# PAM8320_Amplifier_Board_R1.net
KiCad netlist of a schematic drawn in EAGLE
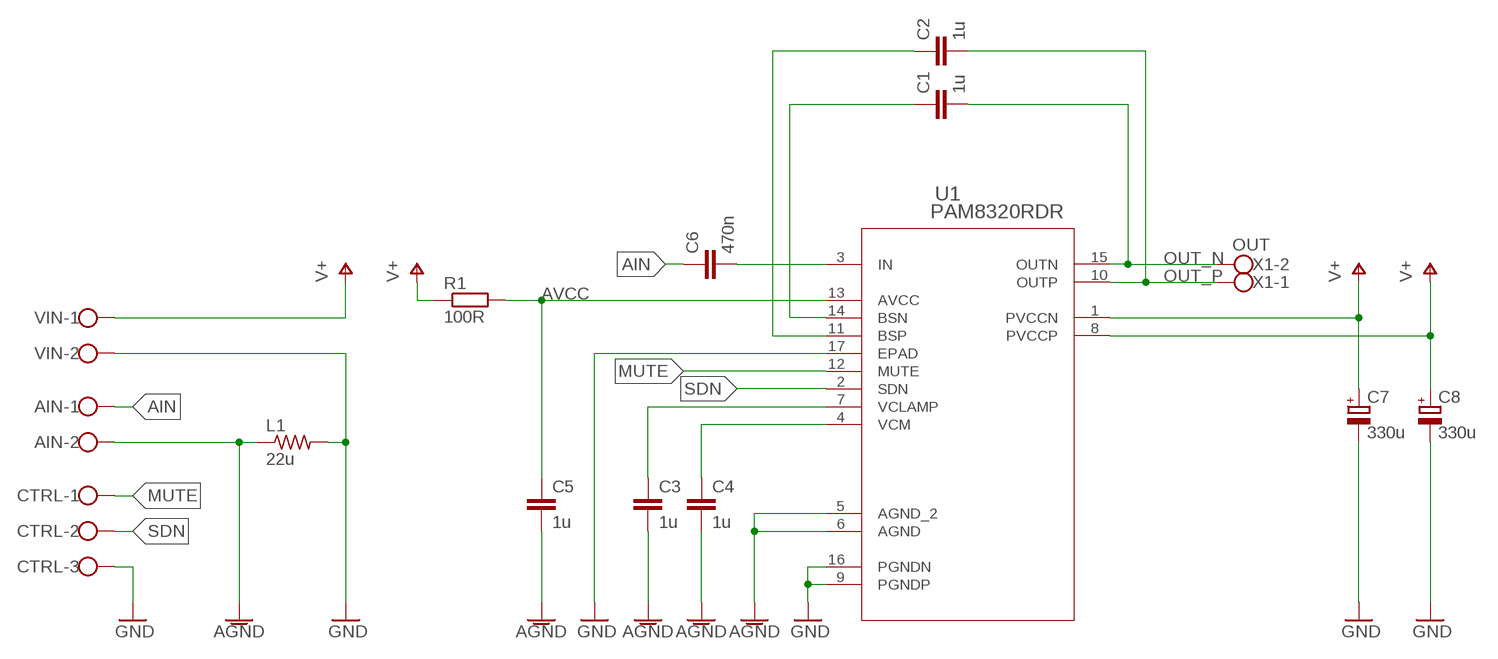
[diagram p0: schematic, sheet 1]

(export (version "E")
  (design (tool "Eeschema 10.0.6"))
  (components
    (comp (ref "AIN")
      (value "W237-102")
      (footprint "eagle-import:W237-102")
      (fields (field (name "MPN") "237-102"))
      (libsource (lib "eagle-import") (part "W237-102"))
    )
    (comp (ref "C1")
      (value "1u")
      (footprint "eagle-import:C1206")
      (libsource (lib "eagle-import") (part "C-EUC1206"))
    )
    (comp (ref "C2")
      (value "1u")
      (footprint "eagle-import:C1206")
      (libsource (lib "eagle-import") (part "C-EUC1206"))
    )
    (comp (ref "C3")
      (value "1u")
      (footprint "eagle-import:C1206")
      (libsource (lib "eagle-import") (part "C-EUC1206"))
    )
    (comp (ref "C4")
      (value "1u")
      (footprint "eagle-import:C1206")
      (libsource (lib "eagle-import") (part "C-EUC1206"))
    )
    (comp (ref "C5")
      (value "1u")
      (footprint "eagle-import:C1206")
      (libsource (lib "eagle-import") (part "C-EUC1206"))
    )
    (comp (ref "C6")
      (value "470n")
      (footprint "eagle-import:C1206")
      (libsource (lib "eagle-import") (part "C-EUC1206"))
    )
    (comp (ref "C7")
      (value "330u")
      (footprint "eagle-import:E3,5-8")
      (libsource (lib "eagle-import") (part "CPOL-EUE3.5-8"))
    )
    (comp (ref "C8")
      (value "330u")
      (footprint "eagle-import:E3,5-8")
      (libsource (lib "eagle-import") (part "CPOL-EUE3.5-8"))
    )
    (comp (ref "CTRL")
      (value "W237-103")
      (footprint "eagle-import:W237-103")
      (fields (field (name "MPN") "237-103"))
      (libsource (lib "eagle-import") (part "W237-103"))
    )
    (comp (ref "L1")
      (value "22u")
      (footprint "eagle-import:R0805")
      (libsource (lib "eagle-import") (part "R-US_R0805"))
    )
    (comp (ref "R1")
      (value "100R")
      (footprint "eagle-import:R0603")
      (libsource (lib "eagle-import") (part "R-EU_R0603"))
    )
    (comp (ref "U1")
      (value "PAM8320RDR")
      (footprint "eagle-import:SO-16EP_3P9X9P9_DIO")
      (fields (field (name "COPYRIGHT") "Copyright (C) 2023 Ultra Librarian. All rights reserved."))
      (libsource (lib "eagle-import") (part "PAM8320RDR"))
    )
    (comp (ref "VIN")
      (value "W237-102")
      (footprint "eagle-import:W237-102")
      (fields (field (name "MPN") "237-102"))
      (libsource (lib "eagle-import") (part "W237-102"))
    )
    (comp (ref "X1")
      (value "OUT")
      (footprint "eagle-import:W237-102")
      (fields (field (name "MPN") "237-102"))
      (libsource (lib "eagle-import") (part "W237-102"))
    )
  )
  (nets
    (net (code "1") (name "/AVCC") (class "Default")
      (node (ref "C5") (pin "1") (pinfunction "1_1") (pintype "passive"))
      (node (ref "R1") (pin "2") (pinfunction "2_2") (pintype "passive"))
      (node (ref "U1") (pin "13") (pinfunction "AVCC_13") (pintype "passive"))
    )
    (net (code "2") (name "/OUT_N") (class "Default")
      (node (ref "C1") (pin "2") (pinfunction "2_2") (pintype "passive"))
      (node (ref "U1") (pin "15") (pinfunction "OUTN_15") (pintype "output"))
      (node (ref "X1") (pin "2") (pinfunction "KL_2") (pintype "passive"))
    )
    (net (code "3") (name "/OUT_P") (class "Default")
      (node (ref "C2") (pin "2") (pinfunction "2_2") (pintype "passive"))
      (node (ref "U1") (pin "10") (pinfunction "OUTP_10") (pintype "output"))
      (node (ref "X1") (pin "1") (pinfunction "KL_1") (pintype "passive"))
    )
    (net (code "4") (name "AGND") (class "Default")
      (node (ref "AIN") (pin "2") (pinfunction "KL_2") (pintype "passive"))
      (node (ref "C3") (pin "2") (pinfunction "2_2") (pintype "passive"))
      (node (ref "C4") (pin "2") (pinfunction "2_2") (pintype "passive"))
      (node (ref "C5") (pin "2") (pinfunction "2_2") (pintype "passive"))
      (node (ref "L1") (pin "1") (pinfunction "1_1") (pintype "passive"))
      (node (ref "U1") (pin "5") (pinfunction "AGND_2_5") (pintype "passive"))
      (node (ref "U1") (pin "6") (pinfunction "AGND_6") (pintype "passive"))
    )
    (net (code "5") (name "AIN") (class "Default")
      (node (ref "AIN") (pin "1") (pinfunction "KL_1") (pintype "passive"))
      (node (ref "C6") (pin "1") (pinfunction "1_1") (pintype "passive"))
    )
    (net (code "6") (name "GND") (class "Default")
      (node (ref "C7") (pin "-") (pinfunction "-_-") (pintype "passive"))
      (node (ref "C8") (pin "-") (pinfunction "-_-") (pintype "passive"))
      (node (ref "CTRL") (pin "3") (pinfunction "KL_3") (pintype "passive"))
      (node (ref "L1") (pin "2") (pinfunction "2_2") (pintype "passive"))
      (node (ref "U1") (pin "16") (pinfunction "PGNDN_16") (pintype "passive"))
      (node (ref "U1") (pin "17") (pinfunction "EPAD_17") (pintype "passive"))
      (node (ref "U1") (pin "9") (pinfunction "PGNDP_9") (pintype "passive"))
      (node (ref "VIN") (pin "2") (pinfunction "KL_2") (pintype "passive"))
    )
    (net (code "7") (name "MUTE") (class "Default")
      (node (ref "CTRL") (pin "1") (pinfunction "KL_1") (pintype "passive"))
      (node (ref "U1") (pin "12") (pinfunction "MUTE_12") (pintype "passive"))
    )
    (net (code "8") (name "Net-(U1-BSN)") (class "Default")
      (node (ref "C1") (pin "1") (pinfunction "1_1") (pintype "passive"))
      (node (ref "U1") (pin "14") (pinfunction "BSN_14") (pintype "passive"))
    )
    (net (code "9") (name "Net-(U1-BSP)") (class "Default")
      (node (ref "C2") (pin "1") (pinfunction "1_1") (pintype "passive"))
      (node (ref "U1") (pin "11") (pinfunction "BSP_11") (pintype "passive"))
    )
    (net (code "10") (name "Net-(U1-IN)") (class "Default")
      (node (ref "C6") (pin "2") (pinfunction "2_2") (pintype "passive"))
      (node (ref "U1") (pin "3") (pinfunction "IN_3") (pintype "passive"))
    )
    (net (code "11") (name "Net-(U1-VCLAMP)") (class "Default")
      (node (ref "C3") (pin "1") (pinfunction "1_1") (pintype "passive"))
      (node (ref "U1") (pin "7") (pinfunction "VCLAMP_7") (pintype "passive"))
    )
    (net (code "12") (name "Net-(U1-VCM)") (class "Default")
      (node (ref "C4") (pin "1") (pinfunction "1_1") (pintype "passive"))
      (node (ref "U1") (pin "4") (pinfunction "VCM_4") (pintype "passive"))
    )
    (net (code "13") (name "SDN") (class "Default")
      (node (ref "CTRL") (pin "2") (pinfunction "KL_2") (pintype "passive"))
      (node (ref "U1") (pin "2") (pinfunction "SDN_2") (pintype "passive"))
    )
    (net (code "14") (name "V+") (class "Default")
      (node (ref "C7") (pin "+") (pinfunction "+_+") (pintype "passive"))
      (node (ref "C8") (pin "+") (pinfunction "+_+") (pintype "passive"))
      (node (ref "R1") (pin "1") (pinfunction "1_1") (pintype "passive"))
      (node (ref "U1") (pin "1") (pinfunction "PVCCN_1") (pintype "passive"))
      (node (ref "U1") (pin "8") (pinfunction "PVCCP_8") (pintype "passive"))
      (node (ref "VIN") (pin "1") (pinfunction "KL_1") (pintype "passive"))
    )
  )
)
